# Evaluation_Sheet.net
KiCad netlist of a schematic drawn in Altium Designer
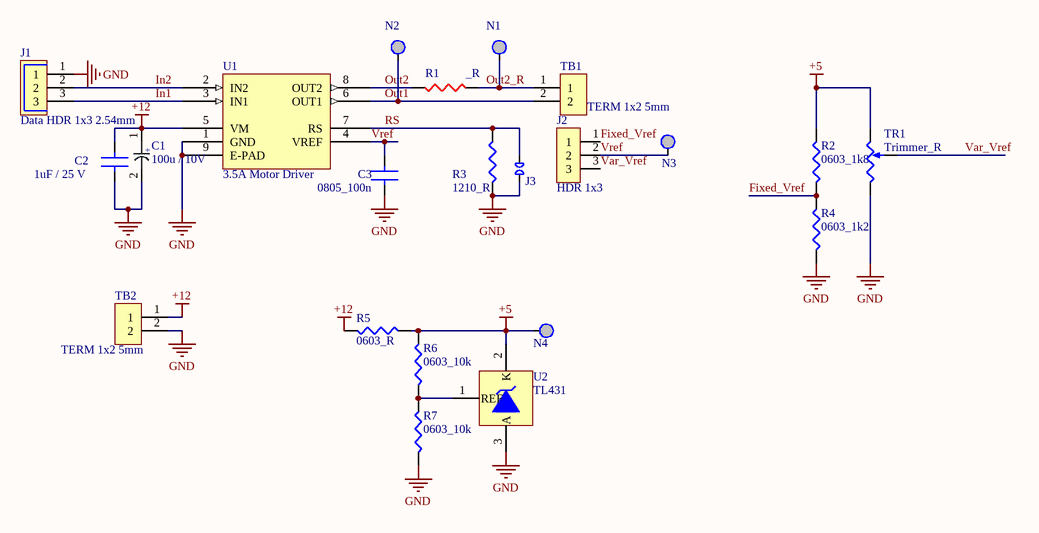
[diagram p0: Evaluation_Sheet.SchDoc]

(export (version "E")
  (design (tool "Eeschema 10.0.6"))
  (components
    (comp (ref "C1")
      (value "100u / 10V")
      (footprint "C_ALUM_D_SIZE")
      (description "Cap Aluminum 100uF 10V 20% (5 X 5.4mm) SMD 50mA 1000 hr 85°C T/R")
      (fields (field (name "TOLERANCE") "20%"))
      (libsource (lib "TimerSMD_Components") (part "EEE-1AA101WR"))
    )
    (comp (ref "C2")
      (value "1uF / 25 V")
      (footprint "C0805 - 0.1uf")
      (fields (field (name "TOLERANCE") "10%") (field (name "VOLTAGE") "25V"))
      (libsource (lib "TimerSMD_Components") (part "C2012X5R1E105K125AA"))
    )
    (comp (ref "C3")
      (value "0805_100n")
      (footprint "C0805 - 0.1uf")
      (fields (field (name "TOLERANCE") "10%") (field (name "VOLTAGE") "25V"))
      (libsource (lib "TimerSMD_Components") (part "C2012X5R1E105K125AA"))
    )
    (comp (ref "J1")
      (value "Data HDR 1x3 2.54mm")
      (footprint "DHDR_1x3_2.54mm")
      (description "03P MTA100 SHRD HDR,W/O PEG SN")
      (libsource (lib "CAD_Symbols") (part "3-Pin Data Connector"))
    )
    (comp (ref "J2")
      (value "HDR 1x3")
      (footprint "HDR 1x3 2.54mm")
      (description "1x3 Male Header 2.54 mm pitch")
      (libsource (lib "CAD_Symbols") (part "HDR 1x3"))
    )
    (comp (ref "J3")
      (value "Jumper Pads")
      (footprint "JMP")
      (libsource (lib "TimerSMD_Components") (part "Jumper Pads"))
    )
    (comp (ref "N1")
      (value "Test Node")
      (footprint "TEST NODE")
      (libsource (lib "TimerSMD_Components") (part "Test Node"))
    )
    (comp (ref "N2")
      (value "Test Node")
      (footprint "TEST NODE")
      (libsource (lib "TimerSMD_Components") (part "Test Node"))
    )
    (comp (ref "N3")
      (value "Test Node")
      (footprint "TEST NODE")
      (libsource (lib "TimerSMD_Components") (part "Test Node"))
    )
    (comp (ref "N4")
      (value "Test Node")
      (footprint "TEST NODE")
      (libsource (lib "TimerSMD_Components") (part "Test Node"))
    )
    (comp (ref "R1")
      (value "_R")
      (footprint "5WATT_RESISTOR")
      (libsource (lib "CAD_Symbols") (part "5W Resistor"))
    )
    (comp (ref "R2")
      (value "0603_1k8")
      (footprint "0603_CAP")
      (libsource (lib "TimerSMD_Components") (part "0603 Resistor"))
    )
    (comp (ref "R3")
      (value "1210_R")
      (footprint "1210_R")
      (libsource (lib "TimerSMD_Components") (part "1210 Resistor"))
    )
    (comp (ref "R4")
      (value "0603_1k2")
      (footprint "0603_CAP")
      (libsource (lib "TimerSMD_Components") (part "0603 Resistor"))
    )
    (comp (ref "R5")
      (value "0603_R")
      (footprint "0603_CAP")
      (libsource (lib "TimerSMD_Components") (part "0603 Resistor"))
    )
    (comp (ref "R6")
      (value "0603_10k")
      (footprint "0603_CAP")
      (libsource (lib "TimerSMD_Components") (part "0603 Resistor"))
    )
    (comp (ref "R7")
      (value "0603_10k")
      (footprint "0603_CAP")
      (libsource (lib "TimerSMD_Components") (part "0603 Resistor"))
    )
    (comp (ref "TB1")
      (value "TERM 1x2 5mm")
      (footprint "Terminal_5mm")
      (fields (field (name "VOLTAGE") "300V"))
      (libsource (lib "") (part "Terminal BLK Green_1"))
    )
    (comp (ref "TB2")
      (value "TERM 1x2 5mm")
      (footprint "Terminal_5mm")
      (fields (field (name "VOLTAGE") "300V"))
      (libsource (lib "CAD_Symbols") (part "Terminal BLK Green"))
    )
    (comp (ref "TR1")
      (value "Trimmer_R")
      (footprint "3296W_TRIMMER")
      (libsource (lib "CAD_Symbols") (part "Blue Trimmer Pot (Small)"))
    )
    (comp (ref "U1")
      (value "3.5A Motor Driver")
      (footprint "HSOP8")
      (libsource (lib "TimerSMD_Components") (part "TB67H450FNG"))
    )
    (comp (ref "U2")
      (value "TL431")
      (footprint "SO-23")
      (description "SMD Voltage References SOT-23")
      (libsource (lib "TimerSMD_Components") (part "TL431"))
    )
  )
  (nets
    (net (code "1") (name "+5") (class "Default")
      (node (ref "N4") (pin "N") (pinfunction "1_N") (pintype "passive"))
      (node (ref "R2") (pin "2") (pinfunction "2_2") (pintype "passive"))
      (node (ref "R5") (pin "2") (pinfunction "2_2") (pintype "passive"))
      (node (ref "R6") (pin "2") (pinfunction "2_2") (pintype "passive"))
      (node (ref "TR1") (pin "1") (pinfunction "1_1") (pintype "passive"))
      (node (ref "U2") (pin "2") (pinfunction "K_2") (pintype "passive"))
    )
    (net (code "2") (name "+12") (class "Default")
      (node (ref "C1") (pin "1") (pinfunction "1_1") (pintype "passive"))
      (node (ref "C2") (pin "2") (pinfunction "2_2") (pintype "passive"))
      (node (ref "R5") (pin "1") (pinfunction "1_1") (pintype "passive"))
      (node (ref "TB2") (pin "1") (pinfunction "1_1") (pintype "passive"))
      (node (ref "U1") (pin "5") (pinfunction "VM_5") (pintype "power_in"))
    )
    (net (code "3") (name "/Fixed_Vref") (class "Default")
      (node (ref "J2") (pin "1") (pinfunction "1_1") (pintype "passive"))
      (node (ref "R2") (pin "1") (pinfunction "1_1") (pintype "passive"))
      (node (ref "R4") (pin "2") (pinfunction "2_2") (pintype "passive"))
    )
    (net (code "4") (name "/In1") (class "Default")
      (node (ref "J1") (pin "3") (pinfunction "3_3") (pintype "passive"))
      (node (ref "U1") (pin "3") (pinfunction "IN1_3") (pintype "input"))
    )
    (net (code "5") (name "/In2") (class "Default")
      (node (ref "J1") (pin "2") (pinfunction "2_2") (pintype "passive"))
      (node (ref "U1") (pin "2") (pinfunction "IN2_2") (pintype "input"))
    )
    (net (code "6") (name "/Out1") (class "Default")
      (node (ref "N2") (pin "N") (pinfunction "1_N") (pintype "passive"))
      (node (ref "TB1") (pin "2") (pinfunction "2_2") (pintype "passive"))
      (node (ref "U1") (pin "6") (pinfunction "OUT1_6") (pintype "output"))
    )
    (net (code "7") (name "/Out2") (class "Default")
      (node (ref "R1") (pin "1") (pinfunction "1_1") (pintype "passive"))
      (node (ref "U1") (pin "8") (pinfunction "OUT2_8") (pintype "output"))
    )
    (net (code "8") (name "/Out2_R") (class "Default")
      (node (ref "N1") (pin "N") (pinfunction "1_N") (pintype "passive"))
      (node (ref "R1") (pin "2") (pinfunction "2_2") (pintype "passive"))
      (node (ref "TB1") (pin "1") (pinfunction "1_1") (pintype "passive"))
    )
    (net (code "9") (name "/RS") (class "Default")
      (node (ref "J3") (pin "2") (pinfunction "2_2") (pintype "passive"))
      (node (ref "R3") (pin "2") (pinfunction "2_2") (pintype "passive"))
      (node (ref "U1") (pin "7") (pinfunction "RS_7") (pintype "passive"))
    )
    (net (code "10") (name "/Var_Vref") (class "Default")
      (node (ref "J2") (pin "3") (pinfunction "3_3") (pintype "passive"))
      (node (ref "TR1") (pin "3") (pinfunction "3_3") (pintype "passive"))
    )
    (net (code "11") (name "/Vref") (class "Default")
      (node (ref "C3") (pin "2") (pinfunction "2_2") (pintype "passive"))
      (node (ref "J2") (pin "2") (pinfunction "2_2") (pintype "passive"))
      (node (ref "N3") (pin "N") (pinfunction "1_N") (pintype "passive"))
      (node (ref "U1") (pin "4") (pinfunction "VREF_4") (pintype "passive"))
    )
    (net (code "12") (name "GND") (class "Default")
      (node (ref "C1") (pin "2") (pinfunction "2_2") (pintype "passive"))
      (node (ref "C2") (pin "1") (pinfunction "1_1") (pintype "passive"))
      (node (ref "C3") (pin "1") (pinfunction "1_1") (pintype "passive"))
      (node (ref "J1") (pin "1") (pinfunction "1_1") (pintype "passive"))
      (node (ref "J3") (pin "1") (pinfunction "1_1") (pintype "passive"))
      (node (ref "R3") (pin "1") (pinfunction "1_1") (pintype "passive"))
      (node (ref "R4") (pin "1") (pinfunction "1_1") (pintype "passive"))
      (node (ref "R7") (pin "1") (pinfunction "1_1") (pintype "passive"))
      (node (ref "TB2") (pin "2") (pinfunction "2_2") (pintype "passive"))
      (node (ref "TR1") (pin "2") (pinfunction "2_2") (pintype "passive"))
      (node (ref "U1") (pin "1") (pinfunction "GND_1") (pintype "power_in"))
      (node (ref "U1") (pin "9") (pinfunction "E-PAD_9") (pintype "power_in"))
      (node (ref "U2") (pin "3") (pinfunction "A_3") (pintype "passive"))
    )
    (net (code "13") (name "Net-(U2-REF)") (class "Default")
      (node (ref "R6") (pin "1") (pinfunction "1_1") (pintype "passive"))
      (node (ref "R7") (pin "2") (pinfunction "2_2") (pintype "passive"))
      (node (ref "U2") (pin "1") (pinfunction "REF_1") (pintype "passive"))
    )
  )
)
